# CAN_Interface.net
KiCad netlist of a schematic drawn in Altium Designer
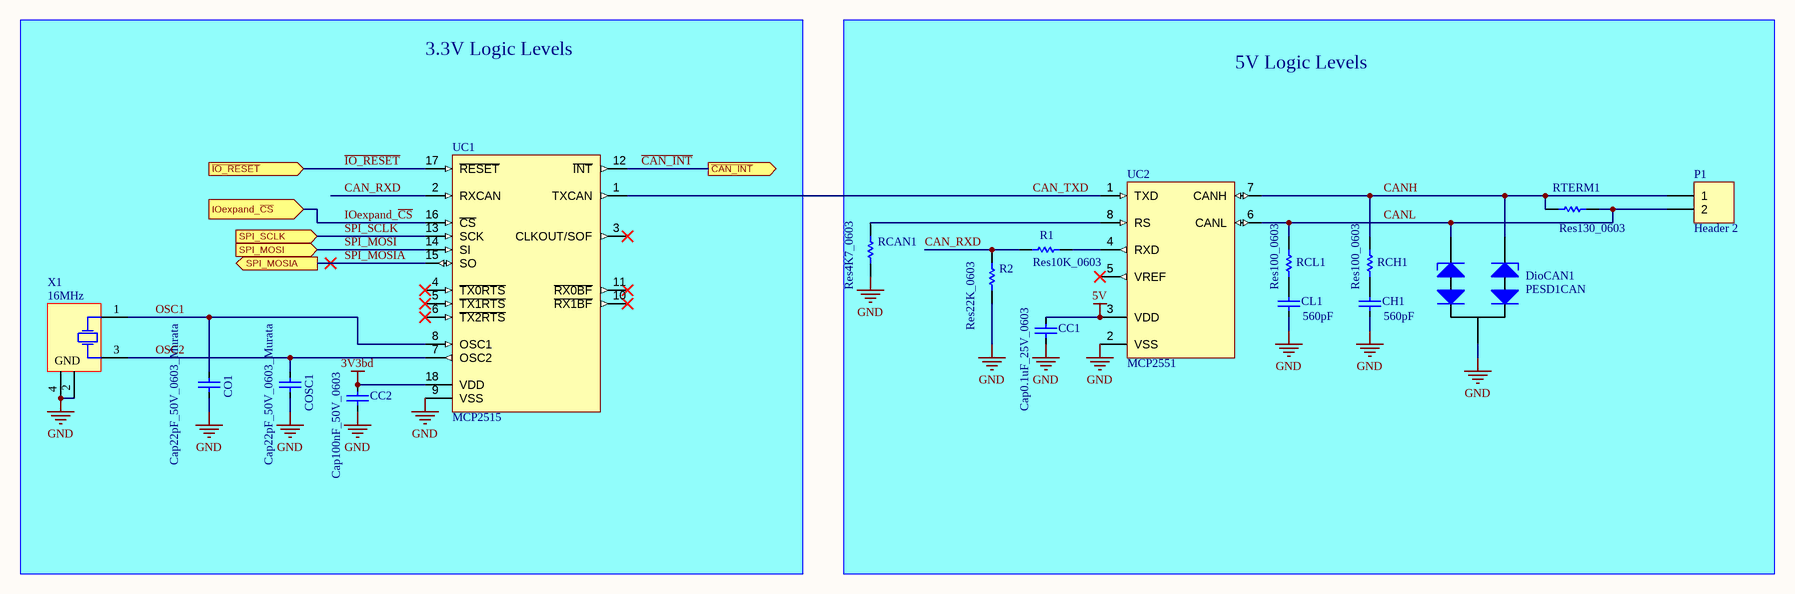
[diagram p0: CAN_Interface.SchDoc]

(export (version "E")
  (design (tool "Eeschema 10.0.6"))
  (components
    (comp (ref "CC1")
      (value "Cap0.1uF_25V_0603")
      (footprint "0603C_L")
      (libsource (lib "Advanced] Training Course - A365") (part "CAP General"))
    )
    (comp (ref "CC2")
      (value "Cap100nF_50V_0603")
      (footprint "0603C_L")
      (libsource (lib "Advanced] Training Course - A365") (part "CAP General"))
    )
    (comp (ref "CH1")
      (value "560pF")
      (footprint "0603C_L")
      (description "560pF 25V 0603")
      (fields (field (name "Comment") "CAP General"))
      (libsource (lib "Advanced] Training Course - A365") (part "CAP General"))
    )
    (comp (ref "CL1")
      (value "560pF")
      (footprint "0603C_L")
      (description "560pF 25V 0603")
      (fields (field (name "Comment") "CAP General"))
      (libsource (lib "Advanced] Training Course - A365") (part "CAP General"))
    )
    (comp (ref "CO1")
      (value "Cap22pF_50V_0603_Murata")
      (footprint "0603C_L")
      (fields (field (name "TOLERANCE") "5%"))
      (libsource (lib "Advanced] Training Course - A365") (part "CAP General"))
    )
    (comp (ref "COSC1")
      (value "Cap22pF_50V_0603_Murata")
      (footprint "0603C_L")
      (fields (field (name "TOLERANCE") "5%"))
      (libsource (lib "Advanced] Training Course - A365") (part "CAP General"))
    )
    (comp (ref "DioCAN1")
      (value "PESD1CAN")
      (footprint "SOT323")
      (description "Trans Voltage Suppressor Diode, 150W, 24V V(RWM), Bidirectional, 2 Element, Silicon")
      (fields (field (name "MANUFACTURER") "Nexperia USA Inc."))
      (libsource (lib "Advanced] Training Course - A365") (part "PESD1CAN"))
    )
    (comp (ref "P1")
      (value "Header 2")
      (footprint "HDR1X2")
      (description "Header, 2-Pin")
      (fields (field (name "PUBLISHER") "Altium Limited"))
      (libsource (lib "Advanced] Training Course - A365") (part "Header 2"))
    )
    (comp (ref "R1")
      (value "Res10K_0603")
      (footprint "0603_L")
      (fields
        (field (name "MANUFACTURER") "Panasonic Electronic Components")
        (field (name "MANUFACTURER PART NUMBER") "ERJ-3GEYJ102V")
        (field (name "TOLERANCE") "5%")
      )
      (libsource (lib "Advanced] Training Course - A365") (part "Resistor General"))
    )
    (comp (ref "R2")
      (value "Res22K_0603")
      (footprint "0603_L")
      (description "RES22K 0.5% 0603")
      (fields
        (field (name "MANUFACTURER") "Yageo")
        (field (name "MANUFACTURER PART NUMBER") "RT0603DRD0722KL")
      )
      (libsource (lib "Advanced] Training Course - A365") (part "Resistor General"))
    )
    (comp (ref "RCAN1")
      (value "Res4K7_0603")
      (footprint "0603_L")
      (fields (field (name "MANUFACTURER") "Yageo") (field (name "TOLERANCE") "0.5%"))
      (libsource (lib "Advanced] Training Course - A365") (part "Resistor General"))
    )
    (comp (ref "RCH1")
      (value "Res100_0603")
      (footprint "0603_L")
      (fields (field (name "MANUFACTURER") "Panasonic Electronic Components") (field (name "TOLERANCE") "5%"))
      (libsource (lib "Advanced] Training Course - A365") (part "Resistor General"))
    )
    (comp (ref "RCL1")
      (value "Res100_0603")
      (footprint "0603_L")
      (fields (field (name "MANUFACTURER") "Panasonic Electronic Components") (field (name "TOLERANCE") "5%"))
      (libsource (lib "Advanced] Training Course - A365") (part "Resistor General"))
    )
    (comp (ref "RTERM1")
      (value "Res130_0603")
      (footprint "0603_L")
      (fields (field (name "MANUFACTURER") "Panasonic Electronic Components") (field (name "TOLERANCE") "5%"))
      (libsource (lib "Advanced] Training Course - A365") (part "Resistor General"))
    )
    (comp (ref "UC1")
      (value "MCP2515")
      (footprint "SOIC-SO18_M")
      (description "Stand-Alone CAN Controller With SPI Interface, 18-Pin SOIC, Extended Temperature")
      (fields
        (field (name "MANUFACTURER") "Microchip")
        (field (name "MANUFACTURER PART NUMBER") "MCP2515-E/SO")
        (field (name "AVAILABLE PREVIEW IMAGES") "2D")
      )
      (libsource (lib "Advanced] Training Course - A365") (part "MCP2515"))
    )
    (comp (ref "UC2")
      (value "MCP2551")
      (footprint "SOIC-SN8_N")
      (description "High-Speed CAN Transceiver, 8-Pin SOIC, Extended Temperature")
      (fields
        (field (name "MANUFACTURER") "Microchip")
        (field (name "MANUFACTURER PART NUMBER") "MCP2551-E/SN")
        (field (name "AVAILABLE PREVIEW IMAGES") "2D")
      )
      (libsource (lib "Advanced] Training Course - A365") (part "MCP2551"))
    )
    (comp (ref "X1")
      (value "Crystal 4Pin")
      (footprint "FP-ABM8-MFG")
      (description "Crystal 16MHz ±20ppm 18pF SMD-4 3.2mm x 2.5mm CSTCE16M0V53-R0 ABM8-16.000MHZ-B2-T")
      (fields (field (name "TOLERANCE") "20ppm") (field (name "FREQUENCY") "16MHz"))
      (libsource (lib " Advanced] Training Course - A365") (part "Crystal 4Pin"))
    )
  )
  (nets
    (net (code "1") (name "/CANH") (class "Default")
      (node (ref "DioCAN1") (pin "1") (pinfunction "A_1") (pintype "passive"))
      (node (ref "P1") (pin "1") (pinfunction "1_1") (pintype "passive"))
      (node (ref "RCH1") (pin "2") (pinfunction "2_2") (pintype "passive"))
      (node (ref "RTERM1") (pin "2") (pinfunction "2_2") (pintype "passive"))
      (node (ref "UC2") (pin "7") (pinfunction "CANH_7") (pintype "bidirectional"))
    )
    (net (code "2") (name "/CANL") (class "Default")
      (node (ref "DioCAN1") (pin "2") (pinfunction "K_2") (pintype "passive"))
      (node (ref "P1") (pin "2") (pinfunction "2_2") (pintype "passive"))
      (node (ref "RCL1") (pin "2") (pinfunction "2_2") (pintype "passive"))
      (node (ref "RTERM1") (pin "1") (pinfunction "1_1") (pintype "passive"))
      (node (ref "UC2") (pin "6") (pinfunction "CANL_6") (pintype "bidirectional"))
    )
    (net (code "3") (name "/CAN_INT") (class "Default")
      (node (ref "UC1") (pin "12") (pinfunction "~{INT}_12") (pintype "output"))
    )
    (net (code "4") (name "/CAN_RXD") (class "Default")
      (node (ref "R1") (pin "2") (pinfunction "2_2") (pintype "passive"))
      (node (ref "R2") (pin "2") (pinfunction "2_2") (pintype "passive"))
      (node (ref "UC1") (pin "2") (pinfunction "RXCAN_2") (pintype "input"))
    )
    (net (code "5") (name "/CAN_TXD") (class "Default")
      (node (ref "UC1") (pin "1") (pinfunction "TXCAN_1") (pintype "output"))
      (node (ref "UC2") (pin "1") (pinfunction "TXD_1") (pintype "input"))
    )
    (net (code "6") (name "/IO_RESET") (class "Default")
      (node (ref "UC1") (pin "17") (pinfunction "~{RESET}_17") (pintype "input"))
    )
    (net (code "7") (name "/IOexpand_~{CS}") (class "Default")
      (node (ref "UC1") (pin "16") (pinfunction "~{CS}_16") (pintype "input"))
    )
    (net (code "8") (name "/OSC1") (class "Default")
      (node (ref "CO1") (pin "2") (pinfunction "2_2") (pintype "passive"))
      (node (ref "UC1") (pin "8") (pinfunction "OSC1_8") (pintype "input"))
      (node (ref "X1") (pin "1") (pinfunction "1_1") (pintype "passive"))
    )
    (net (code "9") (name "/OSC2") (class "Default")
      (node (ref "COSC1") (pin "2") (pinfunction "2_2") (pintype "passive"))
      (node (ref "UC1") (pin "7") (pinfunction "OSC2_7") (pintype "output"))
      (node (ref "X1") (pin "3") (pinfunction "3_3") (pintype "passive"))
    )
    (net (code "10") (name "/SPI_MOSI") (class "Default")
      (node (ref "UC1") (pin "14") (pinfunction "SI_14") (pintype "input"))
    )
    (net (code "11") (name "/SPI_MOSIA") (class "Default")
      (node (ref "UC1") (pin "15") (pinfunction "SO_15") (pintype "bidirectional"))
    )
    (net (code "12") (name "/SPI_SCLK") (class "Default")
      (node (ref "UC1") (pin "13") (pinfunction "SCK_13") (pintype "input"))
    )
    (net (code "13") (name "3V3bd") (class "Default")
      (node (ref "CC2") (pin "2") (pinfunction "2_2") (pintype "passive"))
      (node (ref "UC1") (pin "18") (pinfunction "VDD_18") (pintype "power_in"))
    )
    (net (code "14") (name "5V") (class "Default")
      (node (ref "CC1") (pin "2") (pinfunction "2_2") (pintype "passive"))
      (node (ref "UC2") (pin "3") (pinfunction "VDD_3") (pintype "power_in"))
    )
    (net (code "15") (name "GND") (class "Default")
      (node (ref "CC1") (pin "1") (pinfunction "1_1") (pintype "passive"))
      (node (ref "CC2") (pin "1") (pinfunction "1_1") (pintype "passive"))
      (node (ref "CH1") (pin "2") (pinfunction "2_2") (pintype "passive"))
      (node (ref "CL1") (pin "1") (pinfunction "1_1") (pintype "passive"))
      (node (ref "CO1") (pin "1") (pinfunction "1_1") (pintype "passive"))
      (node (ref "COSC1") (pin "1") (pinfunction "1_1") (pintype "passive"))
      (node (ref "DioCAN1") (pin "3") (pinfunction "3_3") (pintype "passive"))
      (node (ref "R2") (pin "1") (pinfunction "1_1") (pintype "passive"))
      (node (ref "RCAN1") (pin "1") (pinfunction "1_1") (pintype "passive"))
      (node (ref "UC1") (pin "9") (pinfunction "VSS_9") (pintype "power_in"))
      (node (ref "UC2") (pin "2") (pinfunction "VSS_2") (pintype "power_in"))
      (node (ref "X1") (pin "2") (pinfunction "GND_2") (pintype "power_in"))
      (node (ref "X1") (pin "4") (pinfunction "GND_4") (pintype "power_in"))
    )
    (net (code "16") (name "Net-(CH1-Pad1)") (class "Default")
      (node (ref "CH1") (pin "1") (pinfunction "1_1") (pintype "passive"))
      (node (ref "RCH1") (pin "1") (pinfunction "1_1") (pintype "passive"))
    )
    (net (code "17") (name "Net-(CL1-Pad2)") (class "Default")
      (node (ref "CL1") (pin "2") (pinfunction "2_2") (pintype "passive"))
      (node (ref "RCL1") (pin "1") (pinfunction "1_1") (pintype "passive"))
    )
    (net (code "18") (name "Net-(UC2-RS)") (class "Default")
      (node (ref "RCAN1") (pin "2") (pinfunction "2_2") (pintype "passive"))
      (node (ref "UC2") (pin "8") (pinfunction "RS_8") (pintype "input"))
    )
    (net (code "19") (name "Net-(UC2-RXD)") (class "Default")
      (node (ref "R1") (pin "1") (pinfunction "1_1") (pintype "passive"))
      (node (ref "UC2") (pin "4") (pinfunction "RXD_4") (pintype "output"))
    )
    (net (code "20") (name "unconnected-(UC1-CLKOUT{slash}SOF-Pad3)") (class "Default")
      (node (ref "UC1") (pin "3") (pinfunction "CLKOUT/SOF_3") (pintype "output+no_connect"))
    )
    (net (code "21") (name "unconnected-(UC1-~{RX0BF}-Pad11)") (class "Default")
      (node (ref "UC1") (pin "11") (pinfunction "~{RX0BF}_11") (pintype "output+no_connect"))
    )
    (net (code "22") (name "unconnected-(UC1-~{RX1BF}-Pad10)") (class "Default")
      (node (ref "UC1") (pin "10") (pinfunction "~{RX1BF}_10") (pintype "output+no_connect"))
    )
    (net (code "23") (name "unconnected-(UC1-~{TX0RTS}-Pad4)") (class "Default")
      (node (ref "UC1") (pin "4") (pinfunction "~{TX0RTS}_4") (pintype "input+no_connect"))
    )
    (net (code "24") (name "unconnected-(UC1-~{TX1RTS}-Pad5)") (class "Default")
      (node (ref "UC1") (pin "5") (pinfunction "~{TX1RTS}_5") (pintype "input+no_connect"))
    )
    (net (code "25") (name "unconnected-(UC1-~{TX2RTS}-Pad6)") (class "Default")
      (node (ref "UC1") (pin "6") (pinfunction "~{TX2RTS}_6") (pintype "input+no_connect"))
    )
    (net (code "26") (name "unconnected-(UC2-VREF-Pad5)") (class "Default")
      (node (ref "UC2") (pin "5") (pinfunction "VREF_5") (pintype "output+no_connect"))
    )
  )
)
